# implant6.net
KiCad netlist of a schematic drawn in EAGLE
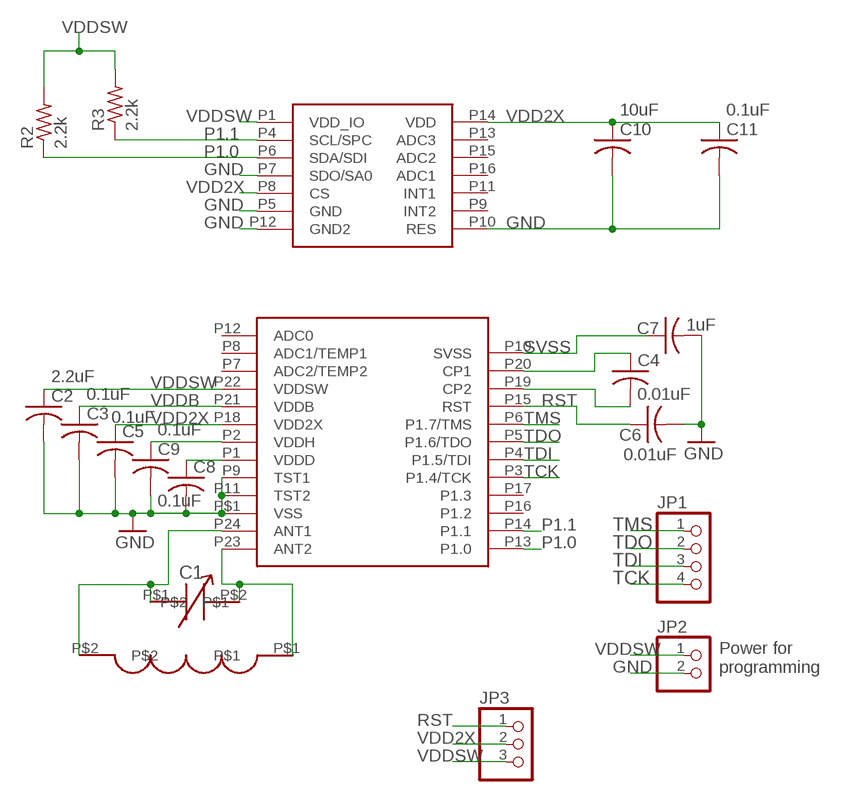
[diagram p0: schematic, sheet 1]

(export (version "E")
  (design (tool "Eeschema 10.0.6"))
  (components
    (comp (ref "C2")
      (value "2.2uF")
      (footprint "eagle-import:C0805")
      (libsource (lib "eagle-import") (part "C-USC0805"))
    )
    (comp (ref "C3")
      (value "0.1uF")
      (footprint "eagle-import:C0805")
      (libsource (lib "eagle-import") (part "C-USC0805"))
    )
    (comp (ref "C4")
      (value "0.01uF")
      (footprint "eagle-import:C0805")
      (libsource (lib "eagle-import") (part "C-USC0805"))
    )
    (comp (ref "C5")
      (value "0.1uF")
      (footprint "eagle-import:C0805")
      (libsource (lib "eagle-import") (part "C-USC0805"))
    )
    (comp (ref "C6")
      (value "0.01uF")
      (footprint "eagle-import:C0805")
      (libsource (lib "eagle-import") (part "C-USC0805"))
    )
    (comp (ref "C7")
      (value "1uF")
      (footprint "eagle-import:C0805")
      (libsource (lib "eagle-import") (part "C-USC0805"))
    )
    (comp (ref "C8")
      (value "0.1uF")
      (footprint "eagle-import:C0805")
      (libsource (lib "eagle-import") (part "C-USC0805"))
    )
    (comp (ref "C9")
      (value "0.1uF")
      (footprint "eagle-import:C0805")
      (libsource (lib "eagle-import") (part "C-USC0805"))
    )
    (comp (ref "C10")
      (value "10uF")
      (footprint "eagle-import:C0805")
      (libsource (lib "eagle-import") (part "C-USC0805"))
    )
    (comp (ref "C11")
      (value "0.1uF")
      (footprint "eagle-import:C0805")
      (libsource (lib "eagle-import") (part "C-USC0805"))
    )
    (comp (ref "JP1")
      (value "PINHD-1X4")
      (footprint "eagle-import:1X04")
      (libsource (lib "eagle-import") (part "PINHD-1X4"))
    )
    (comp (ref "JP2")
      (value "PINHD-1X2")
      (footprint "eagle-import:1X02")
      (libsource (lib "eagle-import") (part "PINHD-1X2"))
    )
    (comp (ref "JP3")
      (value "PINHD-1X3")
      (footprint "eagle-import:1X03")
      (libsource (lib "eagle-import") (part "PINHD-1X3"))
    )
    (comp (ref "R2")
      (value "2.2k")
      (footprint "eagle-import:R0805")
      (libsource (lib "eagle-import") (part "R-US_R0805"))
    )
    (comp (ref "R3")
      (value "2.2k")
      (footprint "eagle-import:R0805")
      (libsource (lib "eagle-import") (part "R-US_R0805"))
    )
    (comp (ref "U$1")
      (value "RF430FRL152H")
      (footprint "eagle-import:VQFN")
      (libsource (lib "eagle-import") (part "RF430FRL152H"))
    )
    (comp (ref "U$2")
      (value "COILCOIL3")
      (footprint "eagle-import:COIL3")
      (libsource (lib "eagle-import") (part "COILCOIL3"))
    )
    (comp (ref "U$3")
      (value "VAR_CAP")
      (footprint "eagle-import:VAR_CAP")
      (libsource (lib "eagle-import") (part "VAR_CAP"))
    )
    (comp (ref "U$4")
      (value "LIS3DH")
      (footprint "eagle-import:LGA-16")
      (libsource (lib "eagle-import") (part "LIS3DH"))
    )
  )
  (nets
    (net (code "1") (name "/P1.0") (class "Default")
      (node (ref "R2") (pin "1") (pinfunction "1_1") (pintype "passive"))
      (node (ref "U$1") (pin "P13") (pinfunction "P1.0_P13") (pintype "bidirectional"))
      (node (ref "U$4") (pin "P6") (pinfunction "SDA/SDI_P6") (pintype "bidirectional"))
    )
    (net (code "2") (name "/P1.1") (class "Default")
      (node (ref "R3") (pin "1") (pinfunction "1_1") (pintype "passive"))
      (node (ref "U$1") (pin "P14") (pinfunction "P1.1_P14") (pintype "bidirectional"))
      (node (ref "U$4") (pin "P4") (pinfunction "SCL/SPC_P4") (pintype "bidirectional"))
    )
    (net (code "3") (name "/RST") (class "Default")
      (node (ref "C6") (pin "1") (pinfunction "1_1") (pintype "passive"))
      (node (ref "JP3") (pin "1") (pinfunction "1_1") (pintype "passive"))
      (node (ref "U$1") (pin "P15") (pinfunction "RST_P15") (pintype "bidirectional"))
    )
    (net (code "4") (name "/SVSS") (class "Default")
      (node (ref "C7") (pin "1") (pinfunction "1_1") (pintype "passive"))
      (node (ref "U$1") (pin "P10") (pinfunction "SVSS_P10") (pintype "bidirectional"))
    )
    (net (code "5") (name "/TCK") (class "Default")
      (node (ref "JP1") (pin "4") (pinfunction "4_4") (pintype "passive"))
      (node (ref "U$1") (pin "P3") (pinfunction "P1.4/TCK_P3") (pintype "bidirectional"))
    )
    (net (code "6") (name "/TDI") (class "Default")
      (node (ref "JP1") (pin "3") (pinfunction "3_3") (pintype "passive"))
      (node (ref "U$1") (pin "P4") (pinfunction "P1.5/TDI_P4") (pintype "bidirectional"))
    )
    (net (code "7") (name "/TDO") (class "Default")
      (node (ref "JP1") (pin "2") (pinfunction "2_2") (pintype "passive"))
      (node (ref "U$1") (pin "P5") (pinfunction "P1.6/TDO_P5") (pintype "bidirectional"))
    )
    (net (code "8") (name "/TMS") (class "Default")
      (node (ref "JP1") (pin "1") (pinfunction "1_1") (pintype "passive"))
      (node (ref "U$1") (pin "P6") (pinfunction "P1.7/TMS_P6") (pintype "bidirectional"))
    )
    (net (code "9") (name "/VDD2X") (class "Default")
      (node (ref "C10") (pin "1") (pinfunction "1_1") (pintype "passive"))
      (node (ref "C11") (pin "1") (pinfunction "1_1") (pintype "passive"))
      (node (ref "C5") (pin "1") (pinfunction "1_1") (pintype "passive"))
      (node (ref "JP3") (pin "2") (pinfunction "2_2") (pintype "passive"))
      (node (ref "U$1") (pin "P18") (pinfunction "VDD2X_P18") (pintype "bidirectional"))
      (node (ref "U$4") (pin "P14") (pinfunction "VDD_P14") (pintype "bidirectional"))
      (node (ref "U$4") (pin "P8") (pinfunction "CS_P8") (pintype "bidirectional"))
    )
    (net (code "10") (name "/VDDB") (class "Default")
      (node (ref "C3") (pin "1") (pinfunction "1_1") (pintype "passive"))
      (node (ref "U$1") (pin "P21") (pinfunction "VDDB_P21") (pintype "bidirectional"))
    )
    (net (code "11") (name "/VDDSW") (class "Default")
      (node (ref "C2") (pin "1") (pinfunction "1_1") (pintype "passive"))
      (node (ref "JP2") (pin "1") (pinfunction "1_1") (pintype "passive"))
      (node (ref "JP3") (pin "3") (pinfunction "3_3") (pintype "passive"))
      (node (ref "R2") (pin "2") (pinfunction "2_2") (pintype "passive"))
      (node (ref "R3") (pin "2") (pinfunction "2_2") (pintype "passive"))
      (node (ref "U$1") (pin "P22") (pinfunction "VDDSW_P22") (pintype "bidirectional"))
      (node (ref "U$4") (pin "P1") (pinfunction "VDD_IO_P1") (pintype "bidirectional"))
    )
    (net (code "12") (name "GND") (class "Default")
      (node (ref "C10") (pin "2") (pinfunction "2_2") (pintype "passive"))
      (node (ref "C11") (pin "2") (pinfunction "2_2") (pintype "passive"))
      (node (ref "C2") (pin "2") (pinfunction "2_2") (pintype "passive"))
      (node (ref "C3") (pin "2") (pinfunction "2_2") (pintype "passive"))
      (node (ref "C5") (pin "2") (pinfunction "2_2") (pintype "passive"))
      (node (ref "C6") (pin "2") (pinfunction "2_2") (pintype "passive"))
      (node (ref "C7") (pin "2") (pinfunction "2_2") (pintype "passive"))
      (node (ref "C8") (pin "2") (pinfunction "2_2") (pintype "passive"))
      (node (ref "C9") (pin "2") (pinfunction "2_2") (pintype "passive"))
      (node (ref "JP2") (pin "2") (pinfunction "2_2") (pintype "passive"))
      (node (ref "U$1") (pin "P$1") (pinfunction "VSS_P$1") (pintype "bidirectional"))
      (node (ref "U$1") (pin "P11") (pinfunction "TST2_P11") (pintype "bidirectional"))
      (node (ref "U$1") (pin "P9") (pinfunction "TST1_P9") (pintype "bidirectional"))
      (node (ref "U$4") (pin "P10") (pinfunction "RES_P10") (pintype "bidirectional"))
      (node (ref "U$4") (pin "P12") (pinfunction "GND2_P12") (pintype "bidirectional"))
      (node (ref "U$4") (pin "P5") (pinfunction "GND_P5") (pintype "bidirectional"))
      (node (ref "U$4") (pin "P7") (pinfunction "SDO/SA0_P7") (pintype "bidirectional"))
    )
    (net (code "13") (name "Net-(U$1-ANT1)") (class "Default")
      (node (ref "U$1") (pin "P24") (pinfunction "ANT1_P24") (pintype "bidirectional"))
      (node (ref "U$2") (pin "P$2") (pinfunction "P$2_P$2") (pintype "bidirectional"))
      (node (ref "U$3") (pin "P$1") (pinfunction "P$1_P$1") (pintype "bidirectional"))
    )
    (net (code "14") (name "Net-(U$1-ANT2)") (class "Default")
      (node (ref "U$1") (pin "P23") (pinfunction "ANT2_P23") (pintype "bidirectional"))
      (node (ref "U$2") (pin "P$1") (pinfunction "P$1_P$1") (pintype "bidirectional"))
      (node (ref "U$3") (pin "P$2") (pinfunction "P$2_P$2") (pintype "bidirectional"))
    )
    (net (code "15") (name "Net-(U$1-CP1)") (class "Default")
      (node (ref "C4") (pin "1") (pinfunction "1_1") (pintype "passive"))
      (node (ref "U$1") (pin "P20") (pinfunction "CP1_P20") (pintype "bidirectional"))
    )
    (net (code "16") (name "Net-(U$1-CP2)") (class "Default")
      (node (ref "C4") (pin "2") (pinfunction "2_2") (pintype "passive"))
      (node (ref "U$1") (pin "P19") (pinfunction "CP2_P19") (pintype "bidirectional"))
    )
    (net (code "17") (name "Net-(U$1-VDDD)") (class "Default")
      (node (ref "C8") (pin "1") (pinfunction "1_1") (pintype "passive"))
      (node (ref "U$1") (pin "P1") (pinfunction "VDDD_P1") (pintype "bidirectional"))
    )
    (net (code "18") (name "Net-(U$1-VDDH)") (class "Default")
      (node (ref "C9") (pin "1") (pinfunction "1_1") (pintype "passive"))
      (node (ref "U$1") (pin "P2") (pinfunction "VDDH_P2") (pintype "bidirectional"))
    )
    (net (code "19") (name "unconnected-(U$1-ADC0-PadP12)") (class "Default")
      (node (ref "U$1") (pin "P12") (pinfunction "ADC0_P12") (pintype "bidirectional"))
    )
    (net (code "20") (name "unconnected-(U$1-ADC1{slash}TEMP1-PadP8)") (class "Default")
      (node (ref "U$1") (pin "P8") (pinfunction "ADC1/TEMP1_P8") (pintype "bidirectional"))
    )
    (net (code "21") (name "unconnected-(U$1-ADC2{slash}TEMP2-PadP7)") (class "Default")
      (node (ref "U$1") (pin "P7") (pinfunction "ADC2/TEMP2_P7") (pintype "bidirectional"))
    )
    (net (code "22") (name "unconnected-(U$1-P1.2-PadP16)") (class "Default")
      (node (ref "U$1") (pin "P16") (pinfunction "P1.2_P16") (pintype "bidirectional"))
    )
    (net (code "23") (name "unconnected-(U$1-P1.3-PadP17)") (class "Default")
      (node (ref "U$1") (pin "P17") (pinfunction "P1.3_P17") (pintype "bidirectional"))
    )
    (net (code "24") (name "unconnected-(U$4-ADC1-PadP16)") (class "Default")
      (node (ref "U$4") (pin "P16") (pinfunction "ADC1_P16") (pintype "bidirectional"))
    )
    (net (code "25") (name "unconnected-(U$4-ADC2-PadP15)") (class "Default")
      (node (ref "U$4") (pin "P15") (pinfunction "ADC2_P15") (pintype "bidirectional"))
    )
    (net (code "26") (name "unconnected-(U$4-ADC3-PadP13)") (class "Default")
      (node (ref "U$4") (pin "P13") (pinfunction "ADC3_P13") (pintype "bidirectional"))
    )
    (net (code "27") (name "unconnected-(U$4-INT1-PadP11)") (class "Default")
      (node (ref "U$4") (pin "P11") (pinfunction "INT1_P11") (pintype "bidirectional"))
    )
    (net (code "28") (name "unconnected-(U$4-INT2-PadP9)") (class "Default")
      (node (ref "U$4") (pin "P9") (pinfunction "INT2_P9") (pintype "bidirectional"))
    )
  )
)
